# ZHSD-DDR3L.net
KiCad netlist of a schematic drawn in Altium Designer
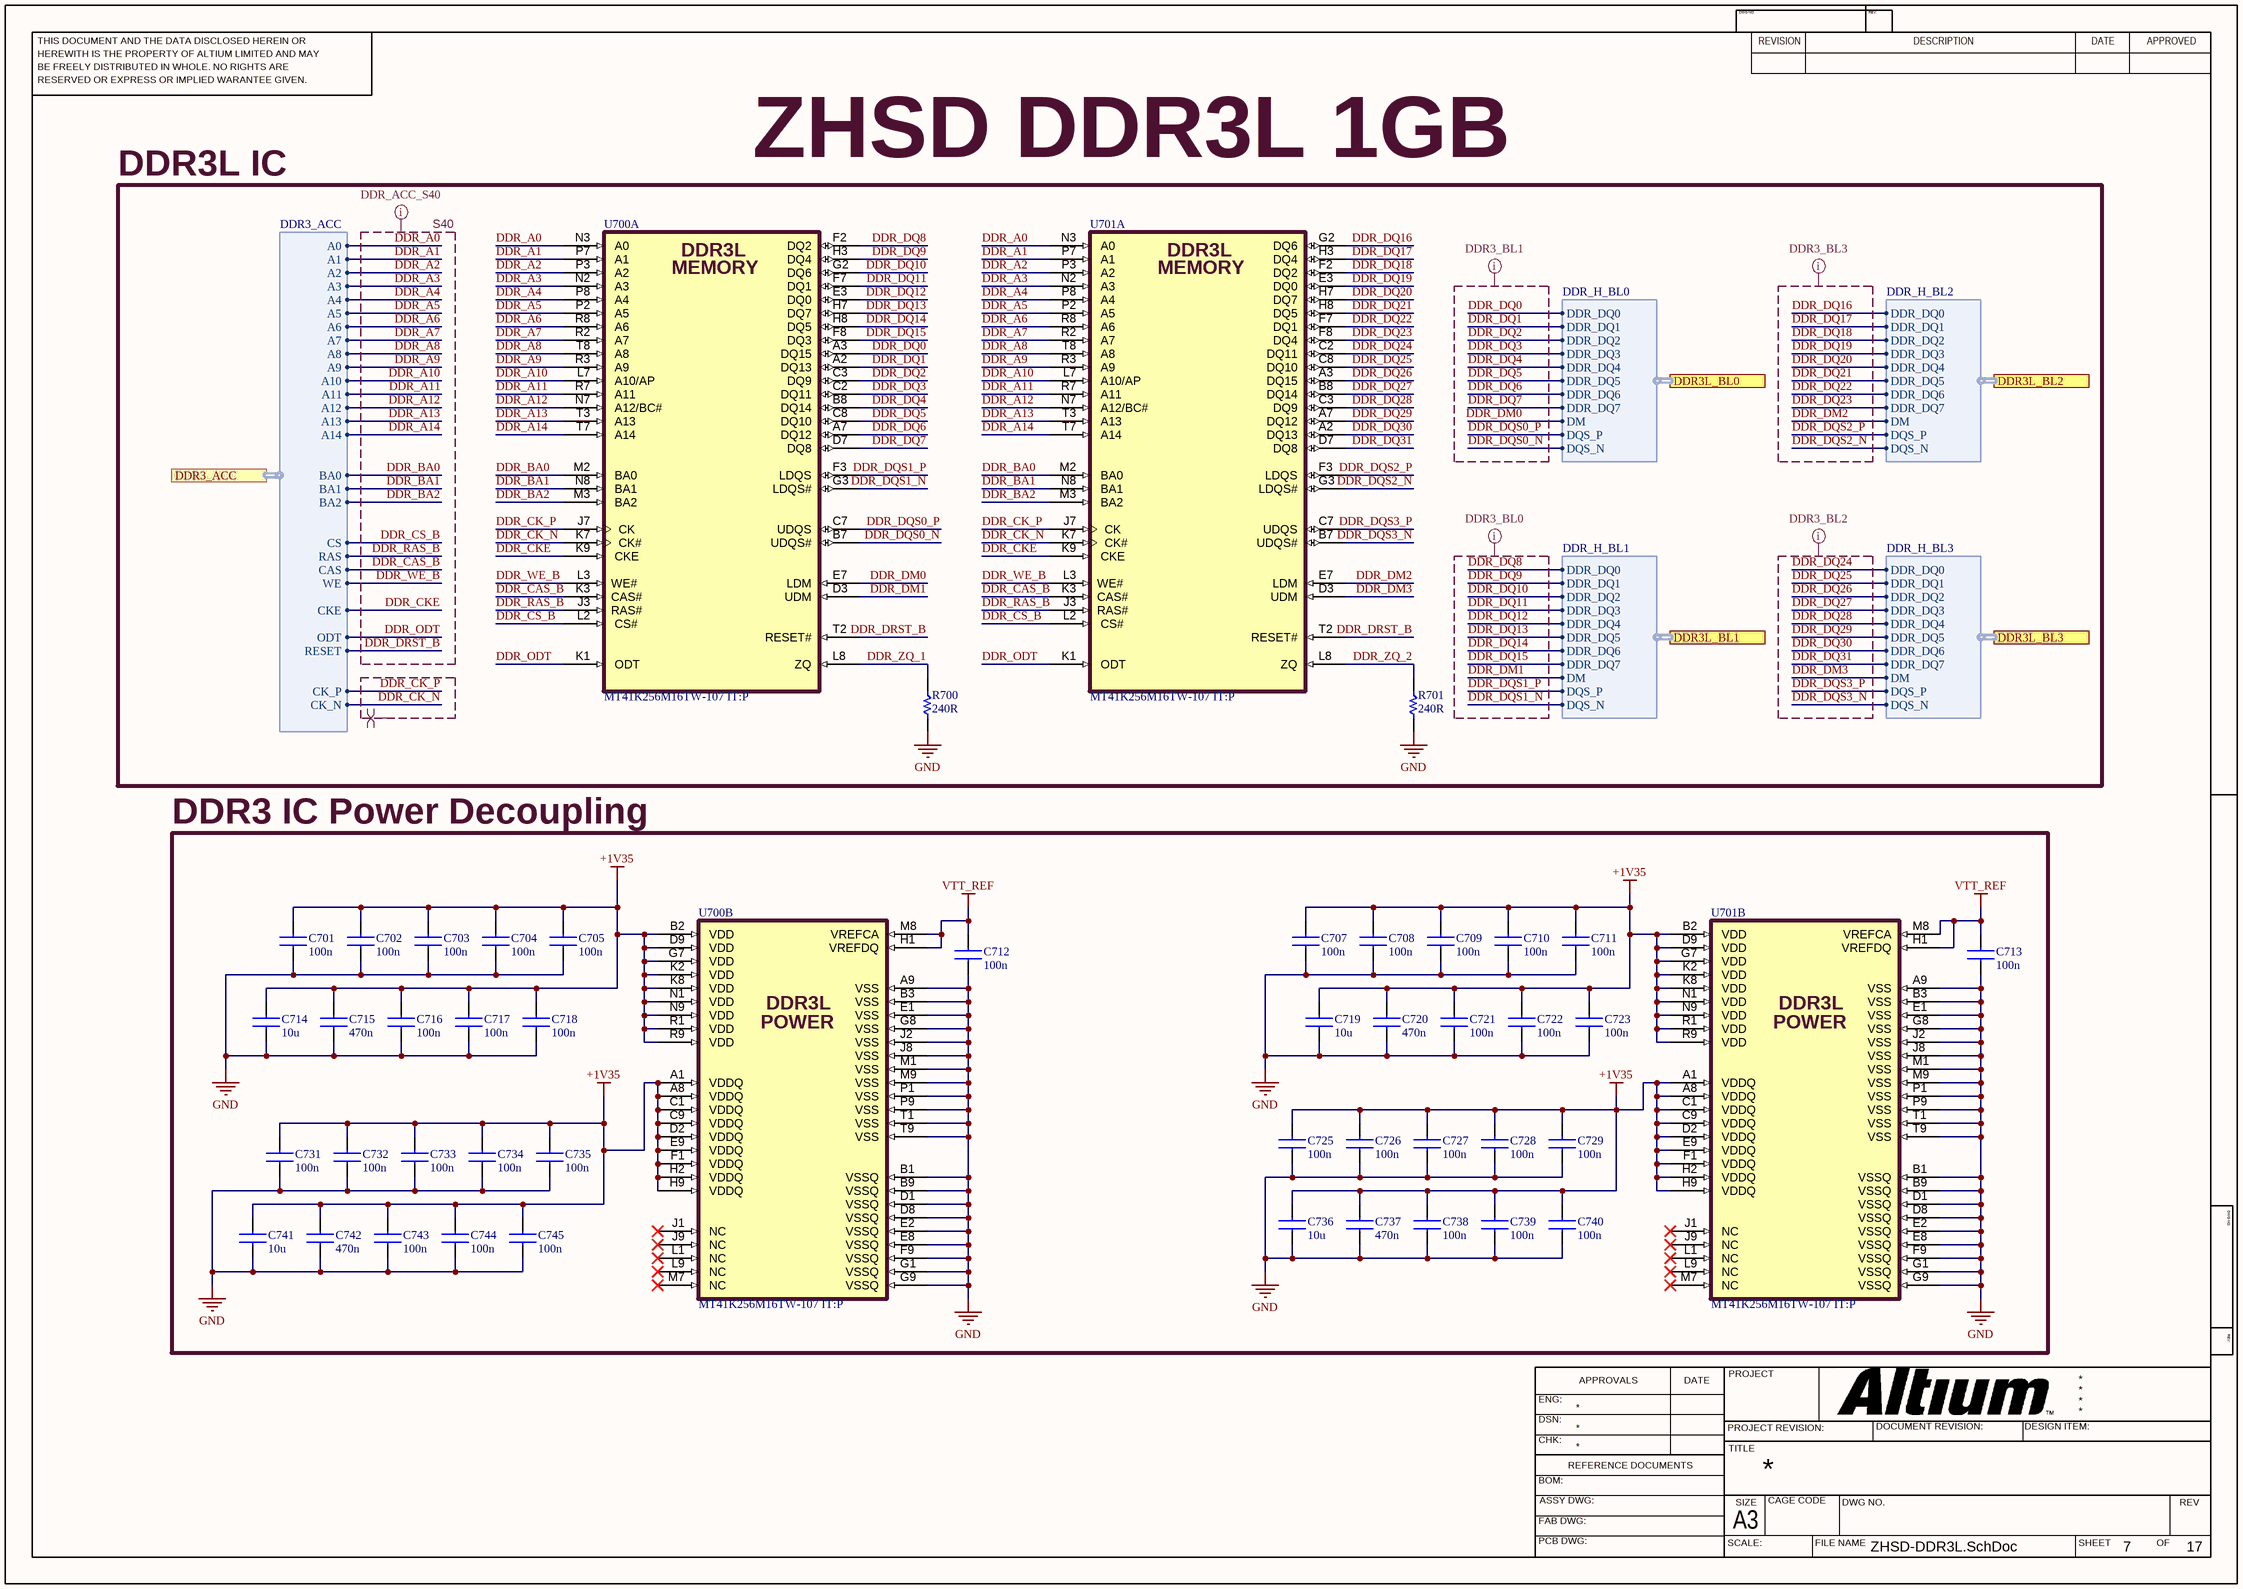
[diagram p0: ZHSD-DDR3L.SchDoc]

(export (version "E")
  (design (tool "Eeschema 10.0.6"))
  (components
    (comp (ref "C701")
      (value "100n")
      (footprint "0402CAPC1005X06N")
      (description "CAP CER 0.1UF 16V X7R 0402 (1005) ±10%")
      (fields (field (name "MANUFACTURER") "Murata Electronics") (field (name "MPN") "GRM155R71C104KA88J"))
      (libsource (lib "UK_Library_SCH") (part "GRM155R71C104KA88J"))
    )
    (comp (ref "C702")
      (value "100n")
      (footprint "0402CAPC1005X06N")
      (description "CAP CER 0.1UF 16V X7R 0402 (1005) ±10%")
      (fields (field (name "MANUFACTURER") "Murata Electronics") (field (name "MPN") "GRM155R71C104KA88J"))
      (libsource (lib "UK_Library_SCH") (part "GRM155R71C104KA88J"))
    )
    (comp (ref "C703")
      (value "100n")
      (footprint "0402CAPC1005X06N")
      (description "CAP CER 0.1UF 16V X7R 0402 (1005) ±10%")
      (fields (field (name "MANUFACTURER") "Murata Electronics") (field (name "MPN") "GRM155R71C104KA88J"))
      (libsource (lib "UK_Library_SCH") (part "GRM155R71C104KA88J"))
    )
    (comp (ref "C704")
      (value "100n")
      (footprint "0402CAPC1005X06N")
      (description "CAP CER 0.1UF 16V X7R 0402 (1005) ±10%")
      (fields (field (name "MANUFACTURER") "Murata Electronics") (field (name "MPN") "GRM155R71C104KA88J"))
      (libsource (lib "UK_Library_SCH") (part "GRM155R71C104KA88J"))
    )
    (comp (ref "C705")
      (value "100n")
      (footprint "0402CAPC1005X06N")
      (description "CAP CER 0.1UF 16V X7R 0402 (1005) ±10%")
      (fields (field (name "MANUFACTURER") "Murata Electronics") (field (name "MPN") "GRM155R71C104KA88J"))
      (libsource (lib "UK_Library_SCH") (part "GRM155R71C104KA88J"))
    )
    (comp (ref "C707")
      (value "100n")
      (footprint "0402CAPC1005X06N")
      (description "CAP CER 0.1UF 16V X7R 0402 (1005) ±10%")
      (fields (field (name "MANUFACTURER") "Murata Electronics") (field (name "MPN") "GRM155R71C104KA88J"))
      (libsource (lib "UK_Library_SCH") (part "GRM155R71C104KA88J"))
    )
    (comp (ref "C708")
      (value "100n")
      (footprint "0402CAPC1005X06N")
      (description "CAP CER 0.1UF 16V X7R 0402 (1005) ±10%")
      (fields (field (name "MANUFACTURER") "Murata Electronics") (field (name "MPN") "GRM155R71C104KA88J"))
      (libsource (lib "UK_Library_SCH") (part "GRM155R71C104KA88J"))
    )
    (comp (ref "C709")
      (value "100n")
      (footprint "0402CAPC1005X06N")
      (description "CAP CER 0.1UF 16V X7R 0402 (1005) ±10%")
      (fields (field (name "MANUFACTURER") "Murata Electronics") (field (name "MPN") "GRM155R71C104KA88J"))
      (libsource (lib "UK_Library_SCH") (part "GRM155R71C104KA88J"))
    )
    (comp (ref "C710")
      (value "100n")
      (footprint "0402CAPC1005X06N")
      (description "CAP CER 0.1UF 16V X7R 0402 (1005) ±10%")
      (fields (field (name "MANUFACTURER") "Murata Electronics") (field (name "MPN") "GRM155R71C104KA88J"))
      (libsource (lib "UK_Library_SCH") (part "GRM155R71C104KA88J"))
    )
    (comp (ref "C711")
      (value "100n")
      (footprint "0402CAPC1005X06N")
      (description "CAP CER 0.1UF 16V X7R 0402 (1005) ±10%")
      (fields (field (name "MANUFACTURER") "Murata Electronics") (field (name "MPN") "GRM155R71C104KA88J"))
      (libsource (lib "UK_Library_SCH") (part "GRM155R71C104KA88J"))
    )
    (comp (ref "C712")
      (value "100n")
      (footprint "0402CAPC1005X06N")
      (description "CAP CER 0.1UF 16V X7R 0402 (1005) ±10%")
      (fields (field (name "MANUFACTURER") "Murata Electronics") (field (name "MPN") "GRM155R71C104KA88J"))
      (libsource (lib "UK_Library_SCH") (part "GRM155R71C104KA88J"))
    )
    (comp (ref "C713")
      (value "100n")
      (footprint "0402CAPC1005X06N")
      (description "CAP CER 0.1UF 16V X7R 0402 (1005) ±10%")
      (fields (field (name "MANUFACTURER") "Murata Electronics") (field (name "MPN") "GRM155R71C104KA88J"))
      (libsource (lib "UK_Library_SCH") (part "GRM155R71C104KA88J"))
    )
    (comp (ref "C714")
      (value "10u")
      (footprint "0603CAPC1608X09N")
      (description "CAP CER 10UF 10V X7R 0603 (1608) ±20%")
      (fields (field (name "MANUFACTURER") "Murata Electronics") (field (name "MPN") "GRM188Z71A106MA73D"))
      (libsource (lib "UK_Library") (part "GRM188Z71A106MA73D"))
    )
    (comp (ref "C715")
      (value "470n")
      (footprint "0402CAPC1005X06N")
      (description "CAP CER 0.47UF 6.3V X5R 0402(1005) ±10%")
      (fields (field (name "MANUFACTURER") "Murata Electronics") (field (name "MPN") "GRM155R60J474KE19D"))
      (libsource (lib "UK_Library") (part "GRM155R60J474KE19D"))
    )
    (comp (ref "C716")
      (value "100n")
      (footprint "0402CAPC1005X06N")
      (description "CAP CER 0.1UF 16V X7R 0402 (1005) ±10%")
      (fields (field (name "MANUFACTURER") "Murata Electronics") (field (name "MPN") "GRM155R71C104KA88J"))
      (libsource (lib "UK_Library_SCH") (part "GRM155R71C104KA88J"))
    )
    (comp (ref "C717")
      (value "100n")
      (footprint "0402CAPC1005X06N")
      (description "CAP CER 0.1UF 16V X7R 0402 (1005) ±10%")
      (fields (field (name "MANUFACTURER") "Murata Electronics") (field (name "MPN") "GRM155R71C104KA88J"))
      (libsource (lib "UK_Library_SCH") (part "GRM155R71C104KA88J"))
    )
    (comp (ref "C718")
      (value "100n")
      (footprint "0402CAPC1005X06N")
      (description "CAP CER 0.1UF 16V X7R 0402 (1005) ±10%")
      (fields (field (name "MANUFACTURER") "Murata Electronics") (field (name "MPN") "GRM155R71C104KA88J"))
      (libsource (lib "UK_Library_SCH") (part "GRM155R71C104KA88J"))
    )
    (comp (ref "C719")
      (value "10u")
      (footprint "0603CAPC1608X09N")
      (description "CAP CER 10UF 10V X7R 0603 (1608) ±20%")
      (fields (field (name "MANUFACTURER") "Murata Electronics") (field (name "MPN") "GRM188Z71A106MA73D"))
      (libsource (lib "UK_Library") (part "GRM188Z71A106MA73D"))
    )
    (comp (ref "C720")
      (value "470n")
      (footprint "0402CAPC1005X06N")
      (description "CAP CER 0.47UF 6.3V X5R 0402(1005) ±10%")
      (fields (field (name "MANUFACTURER") "Murata Electronics") (field (name "MPN") "GRM155R60J474KE19D"))
      (libsource (lib "UK_Library") (part "GRM155R60J474KE19D"))
    )
    (comp (ref "C721")
      (value "100n")
      (footprint "0402CAPC1005X06N")
      (description "CAP CER 0.1UF 16V X7R 0402 (1005) ±10%")
      (fields (field (name "MANUFACTURER") "Murata Electronics") (field (name "MPN") "GRM155R71C104KA88J"))
      (libsource (lib "UK_Library_SCH") (part "GRM155R71C104KA88J"))
    )
    (comp (ref "C722")
      (value "100n")
      (footprint "0402CAPC1005X06N")
      (description "CAP CER 0.1UF 16V X7R 0402 (1005) ±10%")
      (fields (field (name "MANUFACTURER") "Murata Electronics") (field (name "MPN") "GRM155R71C104KA88J"))
      (libsource (lib "UK_Library_SCH") (part "GRM155R71C104KA88J"))
    )
    (comp (ref "C723")
      (value "100n")
      (footprint "0402CAPC1005X06N")
      (description "CAP CER 0.1UF 16V X7R 0402 (1005) ±10%")
      (fields (field (name "MANUFACTURER") "Murata Electronics") (field (name "MPN") "GRM155R71C104KA88J"))
      (libsource (lib "UK_Library_SCH") (part "GRM155R71C104KA88J"))
    )
    (comp (ref "C725")
      (value "100n")
      (footprint "0402CAPC1005X06N")
      (description "CAP CER 0.1UF 16V X7R 0402 (1005) ±10%")
      (fields (field (name "MANUFACTURER") "Murata Electronics") (field (name "MPN") "GRM155R71C104KA88J"))
      (libsource (lib "UK_Library_SCH") (part "GRM155R71C104KA88J"))
    )
    (comp (ref "C726")
      (value "100n")
      (footprint "0402CAPC1005X06N")
      (description "CAP CER 0.1UF 16V X7R 0402 (1005) ±10%")
      (fields (field (name "MANUFACTURER") "Murata Electronics") (field (name "MPN") "GRM155R71C104KA88J"))
      (libsource (lib "UK_Library_SCH") (part "GRM155R71C104KA88J"))
    )
    (comp (ref "C727")
      (value "100n")
      (footprint "0402CAPC1005X06N")
      (description "CAP CER 0.1UF 16V X7R 0402 (1005) ±10%")
      (fields (field (name "MANUFACTURER") "Murata Electronics") (field (name "MPN") "GRM155R71C104KA88J"))
      (libsource (lib "UK_Library_SCH") (part "GRM155R71C104KA88J"))
    )
    (comp (ref "C728")
      (value "100n")
      (footprint "0402CAPC1005X06N")
      (description "CAP CER 0.1UF 16V X7R 0402 (1005) ±10%")
      (fields (field (name "MANUFACTURER") "Murata Electronics") (field (name "MPN") "GRM155R71C104KA88J"))
      (libsource (lib "UK_Library_SCH") (part "GRM155R71C104KA88J"))
    )
    (comp (ref "C729")
      (value "100n")
      (footprint "0402CAPC1005X06N")
      (description "CAP CER 0.1UF 16V X7R 0402 (1005) ±10%")
      (fields (field (name "MANUFACTURER") "Murata Electronics") (field (name "MPN") "GRM155R71C104KA88J"))
      (libsource (lib "UK_Library_SCH") (part "GRM155R71C104KA88J"))
    )
    (comp (ref "C731")
      (value "100n")
      (footprint "0402CAPC1005X06N")
      (description "CAP CER 0.1UF 16V X7R 0402 (1005) ±10%")
      (fields (field (name "MANUFACTURER") "Murata Electronics") (field (name "MPN") "GRM155R71C104KA88J"))
      (libsource (lib "UK_Library_SCH") (part "GRM155R71C104KA88J"))
    )
    (comp (ref "C732")
      (value "100n")
      (footprint "0402CAPC1005X06N")
      (description "CAP CER 0.1UF 16V X7R 0402 (1005) ±10%")
      (fields (field (name "MANUFACTURER") "Murata Electronics") (field (name "MPN") "GRM155R71C104KA88J"))
      (libsource (lib "UK_Library_SCH") (part "GRM155R71C104KA88J"))
    )
    (comp (ref "C733")
      (value "100n")
      (footprint "0402CAPC1005X06N")
      (description "CAP CER 0.1UF 16V X7R 0402 (1005) ±10%")
      (fields (field (name "MANUFACTURER") "Murata Electronics") (field (name "MPN") "GRM155R71C104KA88J"))
      (libsource (lib "UK_Library_SCH") (part "GRM155R71C104KA88J"))
    )
    (comp (ref "C734")
      (value "100n")
      (footprint "0402CAPC1005X06N")
      (description "CAP CER 0.1UF 16V X7R 0402 (1005) ±10%")
      (fields (field (name "MANUFACTURER") "Murata Electronics") (field (name "MPN") "GRM155R71C104KA88J"))
      (libsource (lib "UK_Library_SCH") (part "GRM155R71C104KA88J"))
    )
    (comp (ref "C735")
      (value "100n")
      (footprint "0402CAPC1005X06N")
      (description "CAP CER 0.1UF 16V X7R 0402 (1005) ±10%")
      (fields (field (name "MANUFACTURER") "Murata Electronics") (field (name "MPN") "GRM155R71C104KA88J"))
      (libsource (lib "UK_Library_SCH") (part "GRM155R71C104KA88J"))
    )
    (comp (ref "C736")
      (value "10u")
      (footprint "0603CAPC1608X09N")
      (description "CAP CER 10UF 10V X7R 0603 (1608) ±20%")
      (fields (field (name "MANUFACTURER") "Murata Electronics") (field (name "MPN") "GRM188Z71A106MA73D"))
      (libsource (lib "UK_Library") (part "GRM188Z71A106MA73D"))
    )
    (comp (ref "C737")
      (value "470n")
      (footprint "0402CAPC1005X06N")
      (description "CAP CER 0.47UF 6.3V X5R 0402(1005) ±10%")
      (fields (field (name "MANUFACTURER") "Murata Electronics") (field (name "MPN") "GRM155R60J474KE19D"))
      (libsource (lib "UK_Library") (part "GRM155R60J474KE19D"))
    )
    (comp (ref "C738")
      (value "100n")
      (footprint "0402CAPC1005X06N")
      (description "CAP CER 0.1UF 16V X7R 0402 (1005) ±10%")
      (fields (field (name "MANUFACTURER") "Murata Electronics") (field (name "MPN") "GRM155R71C104KA88J"))
      (libsource (lib "UK_Library_SCH") (part "GRM155R71C104KA88J"))
    )
    (comp (ref "C739")
      (value "100n")
      (footprint "0402CAPC1005X06N")
      (description "CAP CER 0.1UF 16V X7R 0402 (1005) ±10%")
      (fields (field (name "MANUFACTURER") "Murata Electronics") (field (name "MPN") "GRM155R71C104KA88J"))
      (libsource (lib "UK_Library_SCH") (part "GRM155R71C104KA88J"))
    )
    (comp (ref "C740")
      (value "100n")
      (footprint "0402CAPC1005X06N")
      (description "CAP CER 0.1UF 16V X7R 0402 (1005) ±10%")
      (fields (field (name "MANUFACTURER") "Murata Electronics") (field (name "MPN") "GRM155R71C104KA88J"))
      (libsource (lib "UK_Library_SCH") (part "GRM155R71C104KA88J"))
    )
    (comp (ref "C741")
      (value "10u")
      (footprint "0603CAPC1608X09N")
      (description "CAP CER 10UF 10V X7R 0603 (1608) ±20%")
      (fields (field (name "MANUFACTURER") "Murata Electronics") (field (name "MPN") "GRM188Z71A106MA73D"))
      (libsource (lib "UK_Library") (part "GRM188Z71A106MA73D"))
    )
    (comp (ref "C742")
      (value "470n")
      (footprint "0402CAPC1005X06N")
      (description "CAP CER 0.47UF 6.3V X5R 0402(1005) ±10%")
      (fields (field (name "MANUFACTURER") "Murata Electronics") (field (name "MPN") "GRM155R60J474KE19D"))
      (libsource (lib "UK_Library") (part "GRM155R60J474KE19D"))
    )
    (comp (ref "C743")
      (value "100n")
      (footprint "0402CAPC1005X06N")
      (description "CAP CER 0.1UF 16V X7R 0402 (1005) ±10%")
      (fields (field (name "MANUFACTURER") "Murata Electronics") (field (name "MPN") "GRM155R71C104KA88J"))
      (libsource (lib "UK_Library_SCH") (part "GRM155R71C104KA88J"))
    )
    (comp (ref "C744")
      (value "100n")
      (footprint "0402CAPC1005X06N")
      (description "CAP CER 0.1UF 16V X7R 0402 (1005) ±10%")
      (fields (field (name "MANUFACTURER") "Murata Electronics") (field (name "MPN") "GRM155R71C104KA88J"))
      (libsource (lib "UK_Library_SCH") (part "GRM155R71C104KA88J"))
    )
    (comp (ref "C745")
      (value "100n")
      (footprint "0402CAPC1005X06N")
      (description "CAP CER 0.1UF 16V X7R 0402 (1005) ±10%")
      (fields (field (name "MANUFACTURER") "Murata Electronics") (field (name "MPN") "GRM155R71C104KA88J"))
      (libsource (lib "UK_Library_SCH") (part "GRM155R71C104KA88J"))
    )
    (comp (ref "R700")
      (value "240R")
      (footprint "0402RESC1005X04N")
      (description "RES 240 OHM 1% 1/16W 0402 (1005)")
      (fields (field (name "MANUFACTURER") "YAGEO") (field (name "MPN") "RC0402FR-07240RL"))
      (libsource (lib "UK_Library") (part "RC0402FR-07240RL"))
    )
    (comp (ref "R701")
      (value "240R")
      (footprint "0402RESC1005X04N")
      (description "RES 240 OHM 1% 1/16W 0402 (1005)")
      (fields (field (name "MANUFACTURER") "YAGEO") (field (name "MPN") "RC0402FR-07240RL"))
      (libsource (lib "UK_Library") (part "RC0402FR-07240RL"))
    )
    (comp (ref "U700")
      (value "MT41K256M16TW-107 IT:P")
      (footprint "BGA96C80P9X16_900X1400X110")
      (description "SDRAM - DDR3L Memory IC 4Gbit Parallel 933 MHz 20 ns 96-FBGA (8x14)")
      (fields (field (name "MANUFACTURER") "Micron Technology Inc."))
      (libsource (lib "") (part "MT41K256M16TW-107 IT{colon}P_1"))
    )
    (comp (ref "U701")
      (value "MT41K256M16TW-107 IT:P")
      (footprint "BGA96C80P9X16_900X1400X110")
      (description "SDRAM - DDR3L Memory IC 4Gbit Parallel 933 MHz 20 ns 96-FBGA (8x14)")
      (fields (field (name "MANUFACTURER") "Micron Technology Inc."))
      (libsource (lib "UK_Library") (part "MT41K256M16TW-107 IT{colon}P"))
    )
  )
  (nets
    (net (code "6") (name "+1V35") (class "Default")
      (node (ref "C701") (pin "2") (pinfunction "2_2") (pintype "passive"))
      (node (ref "C702") (pin "2") (pinfunction "2_2") (pintype "passive"))
      (node (ref "C703") (pin "2") (pinfunction "2_2") (pintype "passive"))
      (node (ref "C704") (pin "2") (pinfunction "2_2") (pintype "passive"))
      (node (ref "C705") (pin "2") (pinfunction "2_2") (pintype "passive"))
      (node (ref "C707") (pin "2") (pinfunction "2_2") (pintype "passive"))
      (node (ref "C708") (pin "2") (pinfunction "2_2") (pintype "passive"))
      (node (ref "C709") (pin "2") (pinfunction "2_2") (pintype "passive"))
      (node (ref "C710") (pin "2") (pinfunction "2_2") (pintype "passive"))
      (node (ref "C711") (pin "2") (pinfunction "2_2") (pintype "passive"))
      (node (ref "C714") (pin "2") (pinfunction "2_2") (pintype "passive"))
      (node (ref "C715") (pin "2") (pinfunction "2_2") (pintype "passive"))
      (node (ref "C716") (pin "2") (pinfunction "2_2") (pintype "passive"))
      (node (ref "C717") (pin "2") (pinfunction "2_2") (pintype "passive"))
      (node (ref "C718") (pin "2") (pinfunction "2_2") (pintype "passive"))
      (node (ref "C719") (pin "2") (pinfunction "2_2") (pintype "passive"))
      (node (ref "C720") (pin "2") (pinfunction "2_2") (pintype "passive"))
      (node (ref "C721") (pin "2") (pinfunction "2_2") (pintype "passive"))
      (node (ref "C722") (pin "2") (pinfunction "2_2") (pintype "passive"))
      (node (ref "C723") (pin "2") (pinfunction "2_2") (pintype "passive"))
      (node (ref "C725") (pin "2") (pinfunction "2_2") (pintype "passive"))
      (node (ref "C726") (pin "2") (pinfunction "2_2") (pintype "passive"))
      (node (ref "C727") (pin "2") (pinfunction "2_2") (pintype "passive"))
      (node (ref "C728") (pin "2") (pinfunction "2_2") (pintype "passive"))
      (node (ref "C729") (pin "2") (pinfunction "2_2") (pintype "passive"))
      (node (ref "C731") (pin "2") (pinfunction "2_2") (pintype "passive"))
      (node (ref "C732") (pin "2") (pinfunction "2_2") (pintype "passive"))
      (node (ref "C733") (pin "2") (pinfunction "2_2") (pintype "passive"))
      (node (ref "C734") (pin "2") (pinfunction "2_2") (pintype "passive"))
      (node (ref "C735") (pin "2") (pinfunction "2_2") (pintype "passive"))
      (node (ref "C736") (pin "2") (pinfunction "2_2") (pintype "passive"))
      (node (ref "C737") (pin "2") (pinfunction "2_2") (pintype "passive"))
      (node (ref "C738") (pin "2") (pinfunction "2_2") (pintype "passive"))
      (node (ref "C739") (pin "2") (pinfunction "2_2") (pintype "passive"))
      (node (ref "C740") (pin "2") (pinfunction "2_2") (pintype "passive"))
      (node (ref "C741") (pin "2") (pinfunction "2_2") (pintype "passive"))
      (node (ref "C742") (pin "2") (pinfunction "2_2") (pintype "passive"))
      (node (ref "C743") (pin "2") (pinfunction "2_2") (pintype "passive"))
      (node (ref "C744") (pin "2") (pinfunction "2_2") (pintype "passive"))
      (node (ref "C745") (pin "2") (pinfunction "2_2") (pintype "passive"))
      (node (ref "U700") (pin "A1") (pinfunction "_VDDQ_A1") (pintype "input"))
      (node (ref "U700") (pin "A8") (pinfunction "_VDDQ_A8") (pintype "input"))
      (node (ref "U700") (pin "B2") (pinfunction "_VDD_B2") (pintype "input"))
      (node (ref "U700") (pin "C1") (pinfunction "_VDDQ_C1") (pintype "input"))
      (node (ref "U700") (pin "C9") (pinfunction "_VDDQ_C9") (pintype "input"))
      (node (ref "U700") (pin "D2") (pinfunction "_VDDQ_D2") (pintype "input"))
      (node (ref "U700") (pin "D9") (pinfunction "_VDD_D9") (pintype "input"))
      (node (ref "U700") (pin "E9") (pinfunction "_VDDQ_E9") (pintype "input"))
      (node (ref "U700") (pin "F1") (pinfunction "_VDDQ_F1") (pintype "input"))
      (node (ref "U700") (pin "G7") (pinfunction "_VDD_G7") (pintype "input"))
      (node (ref "U700") (pin "H2") (pinfunction "_VDDQ_H2") (pintype "input"))
      (node (ref "U700") (pin "H9") (pinfunction "_VDDQ_H9") (pintype "input"))
      (node (ref "U700") (pin "K2") (pinfunction "_VDD_K2") (pintype "input"))
      (node (ref "U700") (pin "K8") (pinfunction "_VDD_K8") (pintype "input"))
      (node (ref "U700") (pin "N1") (pinfunction "_VDD_N1") (pintype "input"))
      (node (ref "U700") (pin "N9") (pinfunction "_VDD_N9") (pintype "input"))
      (node (ref "U700") (pin "R1") (pinfunction "_VDD_R1") (pintype "input"))
      (node (ref "U700") (pin "R9") (pinfunction "_VDD_R9") (pintype "input"))
      (node (ref "U701") (pin "A1") (pinfunction "_VDDQ_A1") (pintype "input"))
      (node (ref "U701") (pin "A8") (pinfunction "_VDDQ_A8") (pintype "input"))
      (node (ref "U701") (pin "B2") (pinfunction "_VDD_B2") (pintype "input"))
      (node (ref "U701") (pin "C1") (pinfunction "_VDDQ_C1") (pintype "input"))
      (node (ref "U701") (pin "C9") (pinfunction "_VDDQ_C9") (pintype "input"))
      (node (ref "U701") (pin "D2") (pinfunction "_VDDQ_D2") (pintype "input"))
      (node (ref "U701") (pin "D9") (pinfunction "_VDD_D9") (pintype "input"))
      (node (ref "U701") (pin "E9") (pinfunction "_VDDQ_E9") (pintype "input"))
      (node (ref "U701") (pin "F1") (pinfunction "_VDDQ_F1") (pintype "input"))
      (node (ref "U701") (pin "G7") (pinfunction "_VDD_G7") (pintype "input"))
      (node (ref "U701") (pin "H2") (pinfunction "_VDDQ_H2") (pintype "input"))
      (node (ref "U701") (pin "H9") (pinfunction "_VDDQ_H9") (pintype "input"))
      (node (ref "U701") (pin "K2") (pinfunction "_VDD_K2") (pintype "input"))
      (node (ref "U701") (pin "K8") (pinfunction "_VDD_K8") (pintype "input"))
      (node (ref "U701") (pin "N1") (pinfunction "_VDD_N1") (pintype "input"))
      (node (ref "U701") (pin "N9") (pinfunction "_VDD_N9") (pintype "input"))
      (node (ref "U701") (pin "R1") (pinfunction "_VDD_R1") (pintype "input"))
      (node (ref "U701") (pin "R9") (pinfunction "_VDD_R9") (pintype "input"))
    )
    (net (code "7") (name "/DDR_A0") (class "Default")
      (node (ref "U700") (pin "N3") (pinfunction "_A0_N3") (pintype "input"))
      (node (ref "U701") (pin "N3") (pinfunction "_A0_N3") (pintype "input"))
    )
    (net (code "8") (name "/DDR_A1") (class "Default")
      (node (ref "U700") (pin "P7") (pinfunction "_A1_P7") (pintype "input"))
      (node (ref "U701") (pin "P7") (pinfunction "_A1_P7") (pintype "input"))
    )
    (net (code "9") (name "/DDR_A2") (class "Default")
      (node (ref "U700") (pin "P3") (pinfunction "_A2_P3") (pintype "input"))
      (node (ref "U701") (pin "P3") (pinfunction "_A2_P3") (pintype "input"))
    )
    (net (code "10") (name "/DDR_A3") (class "Default")
      (node (ref "U700") (pin "N2") (pinfunction "_A3_N2") (pintype "input"))
      (node (ref "U701") (pin "N2") (pinfunction "_A3_N2") (pintype "input"))
    )
    (net (code "11") (name "/DDR_A4") (class "Default")
      (node (ref "U700") (pin "P8") (pinfunction "_A4_P8") (pintype "input"))
      (node (ref "U701") (pin "P8") (pinfunction "_A4_P8") (pintype "input"))
    )
    (net (code "12") (name "/DDR_A5") (class "Default")
      (node (ref "U700") (pin "P2") (pinfunction "_A5_P2") (pintype "input"))
      (node (ref "U701") (pin "P2") (pinfunction "_A5_P2") (pintype "input"))
    )
    (net (code "13") (name "/DDR_A6") (class "Default")
      (node (ref "U700") (pin "R8") (pinfunction "_A6_R8") (pintype "input"))
      (node (ref "U701") (pin "R8") (pinfunction "_A6_R8") (pintype "input"))
    )
    (net (code "14") (name "/DDR_A7") (class "Default")
      (node (ref "U700") (pin "R2") (pinfunction "_A7_R2") (pintype "input"))
      (node (ref "U701") (pin "R2") (pinfunction "_A7_R2") (pintype "input"))
    )
    (net (code "15") (name "/DDR_A8") (class "Default")
      (node (ref "U700") (pin "T8") (pinfunction "_A8_T8") (pintype "input"))
      (node (ref "U701") (pin "T8") (pinfunction "_A8_T8") (pintype "input"))
    )
    (net (code "16") (name "/DDR_A9") (class "Default")
      (node (ref "U700") (pin "R3") (pinfunction "_A9_R3") (pintype "input"))
      (node (ref "U701") (pin "R3") (pinfunction "_A9_R3") (pintype "input"))
    )
    (net (code "17") (name "/DDR_A10") (class "Default")
      (node (ref "U700") (pin "L7") (pinfunction "_A10/AP_L7") (pintype "input"))
      (node (ref "U701") (pin "L7") (pinfunction "_A10/AP_L7") (pintype "input"))
    )
    (net (code "18") (name "/DDR_A11") (class "Default")
      (node (ref "U700") (pin "R7") (pinfunction "_A11_R7") (pintype "input"))
      (node (ref "U701") (pin "R7") (pinfunction "_A11_R7") (pintype "input"))
    )
    (net (code "19") (name "/DDR_A12") (class "Default")
      (node (ref "U700") (pin "N7") (pinfunction "_A12/BC#_N7") (pintype "input"))
      (node (ref "U701") (pin "N7") (pinfunction "_A12/BC#_N7") (pintype "input"))
    )
    (net (code "20") (name "/DDR_A13") (class "Default")
      (node (ref "U700") (pin "T3") (pinfunction "_A13_T3") (pintype "input"))
      (node (ref "U701") (pin "T3") (pinfunction "_A13_T3") (pintype "input"))
    )
    (net (code "21") (name "/DDR_A14") (class "Default")
      (node (ref "U700") (pin "T7") (pinfunction "_A14_T7") (pintype "input"))
      (node (ref "U701") (pin "T7") (pinfunction "_A14_T7") (pintype "input"))
    )
    (net (code "22") (name "/DDR_BA0") (class "Default")
      (node (ref "U700") (pin "M2") (pinfunction "_BA0_M2") (pintype "input"))
      (node (ref "U701") (pin "M2") (pinfunction "_BA0_M2") (pintype "input"))
    )
    (net (code "23") (name "/DDR_BA1") (class "Default")
      (node (ref "U700") (pin "N8") (pinfunction "_BA1_N8") (pintype "input"))
      (node (ref "U701") (pin "N8") (pinfunction "_BA1_N8") (pintype "input"))
    )
    (net (code "24") (name "/DDR_BA2") (class "Default")
      (node (ref "U700") (pin "M3") (pinfunction "_BA2_M3") (pintype "input"))
      (node (ref "U701") (pin "M3") (pinfunction "_BA2_M3") (pintype "input"))
    )
    (net (code "25") (name "/DDR_CAS_B") (class "Default")
      (node (ref "U700") (pin "K3") (pinfunction "CAS#_K3") (pintype "input"))
      (node (ref "U701") (pin "K3") (pinfunction "CAS#_K3") (pintype "input"))
    )
    (net (code "26") (name "/DDR_CKE") (class "Default")
      (node (ref "U700") (pin "K9") (pinfunction "_CKE_K9") (pintype "input"))
      (node (ref "U701") (pin "K9") (pinfunction "_CKE_K9") (pintype "input"))
    )
    (net (code "27") (name "/DDR_CK_N") (class "Default")
      (node (ref "U700") (pin "K7") (pinfunction "_CK#_K7") (pintype "input"))
      (node (ref "U701") (pin "K7") (pinfunction "_CK#_K7") (pintype "input"))
    )
    (net (code "28") (name "/DDR_CK_P") (class "Default")
      (node (ref "U700") (pin "J7") (pinfunction "_CK_J7") (pintype "input"))
      (node (ref "U701") (pin "J7") (pinfunction "_CK_J7") (pintype "input"))
    )
    (net (code "29") (name "/DDR_CS_B") (class "Default")
      (node (ref "U700") (pin "L2") (pinfunction "_CS#_L2") (pintype "input"))
      (node (ref "U701") (pin "L2") (pinfunction "_CS#_L2") (pintype "input"))
    )
    (net (code "30") (name "/DDR_DM0") (class "Default")
      (node (ref "U700") (pin "E7") (pinfunction "_LDM_E7") (pintype "input"))
    )
    (net (code "31") (name "/DDR_DM1") (class "Default")
      (node (ref "U700") (pin "D3") (pinfunction "_UDM_D3") (pintype "input"))
    )
    (net (code "32") (name "/DDR_DM2") (class "Default")
      (node (ref "U701") (pin "E7") (pinfunction "_LDM_E7") (pintype "input"))
    )
    (net (code "33") (name "/DDR_DM3") (class "Default")
      (node (ref "U701") (pin "D3") (pinfunction "_UDM_D3") (pintype "input"))
    )
    (net (code "34") (name "/DDR_DQ0") (class "Default")
      (node (ref "U700") (pin "A3") (pinfunction "_DQ15_A3") (pintype "bidirectional"))
    )
    (net (code "35") (name "/DDR_DQ1") (class "Default")
      (node (ref "U700") (pin "A2") (pinfunction "_DQ13_A2") (pintype "bidirectional"))
    )
    (net (code "36") (name "/DDR_DQ2") (class "Default")
      (node (ref "U700") (pin "C3") (pinfunction "_DQ9_C3") (pintype "bidirectional"))
    )
    (net (code "37") (name "/DDR_DQ3") (class "Default")
      (node (ref "U700") (pin "C2") (pinfunction "_DQ11_C2") (pintype "bidirectional"))
    )
    (net (code "38") (name "/DDR_DQ4") (class "Default")
      (node (ref "U700") (pin "B8") (pinfunction "_DQ14_B8") (pintype "bidirectional"))
    )
    (net (code "39") (name "/DDR_DQ5") (class "Default")
      (node (ref "U700") (pin "C8") (pinfunction "_DQ10_C8") (pintype "bidirectional"))
    )
    (net (code "40") (name "/DDR_DQ6") (class "Default")
      (node (ref "U700") (pin "A7") (pinfunction "_DQ12_A7") (pintype "bidirectional"))
    )
    (net (code "41") (name "/DDR_DQ7") (class "Default")
      (node (ref "U700") (pin "D7") (pinfunction "_DQ8_D7") (pintype "bidirectional"))
    )
    (net (code "42") (name "/DDR_DQ8") (class "Default")
      (node (ref "U700") (pin "F2") (pinfunction "_DQ2_F2") (pintype "bidirectional"))
    )
    (net (code "43") (name "/DDR_DQ9") (class "Default")
      (node (ref "U700") (pin "H3") (pinfunction "_DQ4_H3") (pintype "bidirectional"))
    )
    (net (code "44") (name "/DDR_DQ10") (class "Default")
      (node (ref "U700") (pin "G2") (pinfunction "_DQ6_G2") (pintype "bidirectional"))
    )
    (net (code "45") (name "/DDR_DQ11") (class "Default")
      (node (ref "U700") (pin "F7") (pinfunction "_DQ1_F7") (pintype "bidirectional"))
    )
    (net (code "46") (name "/DDR_DQ12") (class "Default")
      (node (ref "U700") (pin "E3") (pinfunction "_DQ0_E3") (pintype "bidirectional"))
    )
    (net (code "47") (name "/DDR_DQ13") (class "Default")
      (node (ref "U700") (pin "H7") (pinfunction "_DQ7_H7") (pintype "bidirectional"))
    )
    (net (code "48") (name "/DDR_DQ14") (class "Default")
      (node (ref "U700") (pin "H8") (pinfunction "_DQ5_H8") (pintype "bidirectional"))
    )
    (net (code "49") (name "/DDR_DQ15") (class "Default")
      (node (ref "U700") (pin "F8") (pinfunction "_DQ3_F8") (pintype "bidirectional"))
    )
    (net (code "50") (name "/DDR_DQ16") (class "Default")
      (node (ref "U701") (pin "G2") (pinfunction "_DQ6_G2") (pintype "bidirectional"))
    )
    (net (code "51") (name "/DDR_DQ17") (class "Default")
      (node (ref "U701") (pin "H3") (pinfunction "_DQ4_H3") (pintype "bidirectional"))
    )
    (net (code "52") (name "/DDR_DQ18") (class "Default")
      (node (ref "U701") (pin "F2") (pinfunction "_DQ2_F2") (pintype "bidirectional"))
    )
    (net (code "53") (name "/DDR_DQ19") (class "Default")
      (node (ref "U701") (pin "E3") (pinfunction "_DQ0_E3") (pintype "bidirectional"))
    )
    (net (code "54") (name "/DDR_DQ20") (class "Default")
      (node (ref "U701") (pin "H7") (pinfunction "_DQ7_H7") (pintype "bidirectional"))
    )
    (net (code "55") (name "/DDR_DQ21") (class "Default")
      (node (ref "U701") (pin "H8") (pinfunction "_DQ5_H8") (pintype "bidirectional"))
    )
    (net (code "56") (name "/DDR_DQ22") (class "Default")
      (node (ref "U701") (pin "F7") (pinfunction "_DQ1_F7") (pintype "bidirectional"))
    )
    (net (code "57") (name "/DDR_DQ23") (class "Default")
      (node (ref "U701") (pin "F8") (pinfunction "_DQ4_F8") (pintype "bidirectional"))
    )
    (net (code "58") (name "/DDR_DQ24") (class "Default")
      (node (ref "U701") (pin "C2") (pinfunction "_DQ11_C2") (pintype "bidirectional"))
    )
    (net (code "59") (name "/DDR_DQ25") (class "Default")
      (node (ref "U701") (pin "C8") (pinfunction "_DQ10_C8") (pintype "bidirectional"))
    )
    (net (code "60") (name "/DDR_DQ26") (class "Default")
      (node (ref "U701") (pin "A3") (pinfunction "_DQ15_A3") (pintype "bidirectional"))
    )
    (net (code "61") (name "/DDR_DQ27") (class "Default")
      (node (ref "U701") (pin "B8") (pinfunction "_DQ14_B8") (pintype "bidirectional"))
    )
    (net (code "62") (name "/DDR_DQ28") (class "Default")
      (node (ref "U701") (pin "C3") (pinfunction "_DQ9_C3") (pintype "bidirectional"))
    )
    (net (code "63") (name "/DDR_DQ29") (class "Default")
      (node (ref "U701") (pin "A7") (pinfunction "_DQ12_A7") (pintype "bidirectional"))
    )
    (net (code "64") (name "/DDR_DQ30") (class "Default")
      (node (ref "U701") (pin "A2") (pinfunction "_DQ13_A2") (pintype "bidirectional"))
    )
    (net (code "65") (name "/DDR_DQ31") (class "Default")
      (node (ref "U701") (pin "D7") (pinfunction "_DQ8_D7") (pintype "bidirectional"))
    )
    (net (code "66") (name "/DDR_DQS0_N") (class "Default")
      (node (ref "U700") (pin "B7") (pinfunction "_UDQS#_B7") (pintype "bidirectional"))
    )
    (net (code "67") (name "/DDR_DQS0_P") (class "Default")
      (node (ref "U700") (pin "C7") (pinfunction "_UDQS_C7") (pintype "bidirectional"))
    )
    (net (code "68") (name "/DDR_DQS1_N") (class "Default")
      (node (ref "U700") (pin "G3") (pinfunction "_LDQS#_G3") (pintype "bidirectional"))
    )
    (net (code "69") (name "/DDR_DQS1_P") (class "Default")
      (node (ref "U700") (pin "F3") (pinfunction "_LDQS_F3") (pintype "bidirectional"))
    )
    (net (code "70") (name "/DDR_DQS2_N") (class "Default")
      (node (ref "U701") (pin "G3") (pinfunction "_LDQS#_G3") (pintype "bidirectional"))
    )
    (net (code "71") (name "/DDR_DQS2_P") (class "Default")
      (node (ref "U701") (pin "F3") (pinfunction "_LDQS_F3") (pintype "bidirectional"))
    )
    (net (code "72") (name "/DDR_DQS3_N") (class "Default")
      (node (ref "U701") (pin "B7") (pinfunction "_UDQS#_B7") (pintype "bidirectional"))
    )
    (net (code "73") (name "/DDR_DQS3_P") (class "Default")
      (node (ref "U701") (pin "C7") (pinfunction "_UDQS_C7") (pintype "bidirectional"))
    )
    (net (code "74") (name "/DDR_DRST_B") (class "Default")
      (node (ref "U700") (pin "T2") (pinfunction "_RESET#_T2") (pintype "input"))
      (node (ref "U701") (pin "T2") (pinfunction "_RESET#_T2") (pintype "input"))
    )
    (net (code "75") (name "/DDR_ODT") (class "Default")
      (node (ref "U700") (pin "K1") (pinfunction "_ODT_K1") (pintype "input"))
      (node (ref "U701") (pin "K1") (pinfunction "_ODT_K1") (pintype "input"))
    )
    (net (code "76") (name "/DDR_RAS_B") (class "Default")
      (node (ref "U700") (pin "J3") (pinfunction "RAS#_J3") (pintype "input"))
      (node (ref "U701") (pin "J3") (pinfunction "RAS#_J3") (pintype "input"))
    )
    (net (code "77") (name "/DDR_WE_B") (class "Default")
      (node (ref "U700") (pin "L3") (pinfunction "WE#_L3") (pintype "input"))
      (node (ref "U701") (pin "L3") (pinfunction "WE#_L3") (pintype "input"))
    )
    (net (code "78") (name "/DDR_ZQ_1") (class "Default")
      (node (ref "R700") (pin "2") (pinfunction "2_2") (pintype "passive"))
      (node (ref "U700") (pin "L8") (pinfunction "ZQ_L8") (pintype "input"))
    )
    (net (code "79") (name "/DDR_ZQ_2") (class "Default")
      (node (ref "R701") (pin "2") (pinfunction "2_2") (pintype "passive"))
      (node (ref "U701") (pin "L8") (pinfunction "ZQ_L8") (pintype "input"))
    )
    (net (code "85") (name "GND") (class "Default")
      (node (ref "C701") (pin "1") (pinfunction "1_1") (pintype "passive"))
      (node (ref "C702") (pin "1") (pinfunction "1_1") (pintype "passive"))
      (node (ref "C703") (pin "1") (pinfunction "1_1") (pintype "passive"))
      (node (ref "C704") (pin "1") (pinfunction "1_1") (pintype "passive"))
      (node (ref "C705") (pin "1") (pinfunction "1_1") (pintype "passive"))
      (node (ref "C707") (pin "1") (pinfunction "1_1") (pintype "passive"))
      (node (ref "C708") (pin "1") (pinfunction "1_1") (pintype "passive"))
      (node (ref "C709") (pin "1") (pinfunction "1_1") (pintype "passive"))
      (node (ref "C710") (pin "1") (pinfunction "1_1") (pintype "passive"))
      (node (ref "C711") (pin "1") (pinfunction "1_1") (pintype "passive"))
      (node (ref "C712") (pin "1") (pinfunction "1_1") (pintype "passive"))
      (node (ref "C713") (pin "1") (pinfunction "1_1") (pintype "passive"))
      (node (ref "C714") (pin "1") (pinfunction "1_1") (pintype "passive"))
      (node (ref "C715") (pin "1") (pinfunction "1_1") (pintype "passive"))
      (node (ref "C716") (pin "1") (pinfunction "1_1") (pintype "passive"))
      (node (ref "C717") (pin "1") (pinfunction "1_1") (pintype "passive"))
      (node (ref "C718") (pin "1") (pinfunction "1_1") (pintype "passive"))
      (node (ref "C719") (pin "1") (pinfunction "1_1") (pintype "passive"))
      (node (ref "C720") (pin "1") (pinfunction "1_1") (pintype "passive"))
      (node (ref "C721") (pin "1") (pinfunction "1_1") (pintype "passive"))
      (node (ref "C722") (pin "1") (pinfunction "1_1") (pintype "passive"))
      (node (ref "C723") (pin "1") (pinfunction "1_1") (pintype "passive"))
      (node (ref "C725") (pin "1") (pinfunction "1_1") (pintype "passive"))
      (node (ref "C726") (pin "1") (pinfunction "1_1") (pintype "passive"))
      (node (ref "C727") (pin "1") (pinfunction "1_1") (pintype "passive"))
      (node (ref "C728") (pin "1") (pinfunction "1_1") (pintype "passive"))
      (node (ref "C729") (pin "1") (pinfunction "1_1") (pintype "passive"))
      (node (ref "C731") (pin "1") (pinfunction "1_1") (pintype "passive"))
      (node (ref "C732") (pin "1") (pinfunction "1_1") (pintype "passive"))
      (node (ref "C733") (pin "1") (pinfunction "1_1") (pintype "passive"))
      (node (ref "C734") (pin "1") (pinfunction "1_1") (pintype "passive"))
      (node (ref "C735") (pin "1") (pinfunction "1_1") (pintype "passive"))
      (node (ref "C736") (pin "1") (pinfunction "1_1") (pintype "passive"))
      (node (ref "C737") (pin "1") (pinfunction "1_1") (pintype "passive"))
      (node (ref "C738") (pin "1") (pinfunction "1_1") (pintype "passive"))
      (node (ref "C739") (pin "1") (pinfunction "1_1") (pintype "passive"))
      (node (ref "C740") (pin "1") (pinfunction "1_1") (pintype "passive"))
      (node (ref "C741") (pin "1") (pinfunction "1_1") (pintype "passive"))
      (node (ref "C742") (pin "1") (pinfunction "1_1") (pintype "passive"))
      (node (ref "C743") (pin "1") (pinfunction "1_1") (pintype "passive"))
      (node (ref "C744") (pin "1") (pinfunction "1_1") (pintype "passive"))
      (node (ref "C745") (pin "1") (pinfunction "1_1") (pintype "passive"))
      (node (ref "R700") (pin "1") (pinfunction "1_1") (pintype "passive"))
      (node (ref "R701") (pin "1") (pinfunction "1_1") (pintype "passive"))
      (node (ref "U700") (pin "A9") (pinfunction "_VSS_A9") (pintype "input"))
      (node (ref "U700") (pin "B1") (pinfunction "_VSSQ_B1") (pintype "input"))
      (node (ref "U700") (pin "B3") (pinfunction "_VSS_B3") (pintype "input"))
      (node (ref "U700") (pin "B9") (pinfunction "_VSSQ_B9") (pintype "input"))
      (node (ref "U700") (pin "D1") (pinfunction "_VSSQ_D1") (pintype "input"))
      (node (ref "U700") (pin "D8") (pinfunction "_VSSQ_D8") (pintype "input"))
      (node (ref "U700") (pin "E1") (pinfunction "_VSS_E1") (pintype "input"))
      (node (ref "U700") (pin "E2") (pinfunction "_VSSQ_E2") (pintype "input"))
      (node (ref "U700") (pin "E8") (pinfunction "_VSSQ_E8") (pintype "input"))
      (node (ref "U700") (pin "F9") (pinfunction "_VSSQ_F9") (pintype "input"))
      (node (ref "U700") (pin "G1") (pinfunction "_VSSQ_G1") (pintype "input"))
      (node (ref "U700") (pin "G8") (pinfunction "_VSS_G8") (pintype "input"))
      (node (ref "U700") (pin "G9") (pinfunction "_VSSQ_G9") (pintype "input"))
      (node (ref "U700") (pin "J2") (pinfunction "_VSS_J2") (pintype "input"))
      (node (ref "U700") (pin "J8") (pinfunction "_VSS_J8") (pintype "input"))
      (node (ref "U700") (pin "M1") (pinfunction "_VSS_M1") (pintype "input"))
      (node (ref "U700") (pin "M9") (pinfunction "_VSS_M9") (pintype "input"))
      (node (ref "U700") (pin "P1") (pinfunction "_VSS_P1") (pintype "input"))
      (node (ref "U700") (pin "P9") (pinfunction "_VSS_P9") (pintype "input"))
      (node (ref "U700") (pin "T1") (pinfunction "_VSS_T1") (pintype "input"))
      (node (ref "U700") (pin "T9") (pinfunction "_VSS_T9") (pintype "input"))
      (node (ref "U701") (pin "A9") (pinfunction "_VSS_A9") (pintype "input"))
      (node (ref "U701") (pin "B1") (pinfunction "_VSSQ_B1") (pintype "input"))
      (node (ref "U701") (pin "B3") (pinfunction "_VSS_B3") (pintype "input"))
      (node (ref "U701") (pin "B9") (pinfunction "_VSSQ_B9") (pintype "input"))
      (node (ref "U701") (pin "D1") (pinfunction "_VSSQ_D1") (pintype "input"))
      (node (ref "U701") (pin "D8") (pinfunction "_VSSQ_D8") (pintype "input"))
      (node (ref "U701") (pin "E1") (pinfunction "_VSS_E1") (pintype "input"))
      (node (ref "U701") (pin "E2") (pinfunction "_VSSQ_E2") (pintype "input"))
      (node (ref "U701") (pin "E8") (pinfunction "_VSSQ_E8") (pintype "input"))
      (node (ref "U701") (pin "F9") (pinfunction "_VSSQ_F9") (pintype "input"))
      (node (ref "U701") (pin "G1") (pinfunction "_VSSQ_G1") (pintype "input"))
      (node (ref "U701") (pin "G8") (pinfunction "_VSS_G8") (pintype "input"))
      (node (ref "U701") (pin "G9") (pinfunction "_VSSQ_G9") (pintype "input"))
      (node (ref "U701") (pin "J2") (pinfunction "_VSS_J2") (pintype "input"))
      (node (ref "U701") (pin "J8") (pinfunction "_VSS_J8") (pintype "input"))
      (node (ref "U701") (pin "M1") (pinfunction "_VSS_M1") (pintype "input"))
      (node (ref "U701") (pin "M9") (pinfunction "_VSS_M9") (pintype "input"))
      (node (ref "U701") (pin "P1") (pinfunction "_VSS_P1") (pintype "input"))
      (node (ref "U701") (pin "P9") (pinfunction "_VSS_P9") (pintype "input"))
      (node (ref "U701") (pin "T1") (pinfunction "_VSS_T1") (pintype "input"))
      (node (ref "U701") (pin "T9") (pinfunction "_VSS_T9") (pintype "input"))
    )
    (net (code "86") (name "VTT_REF") (class "Default")
      (node (ref "C712") (pin "2") (pinfunction "2_2") (pintype "passive"))
      (node (ref "C713") (pin "2") (pinfunction "2_2") (pintype "passive"))
      (node (ref "U700") (pin "H1") (pinfunction "_VREFDQ_H1") (pintype "input"))
      (node (ref "U700") (pin "M8") (pinfunction "_VREFCA_M8") (pintype "input"))
      (node (ref "U701") (pin "H1") (pinfunction "_VREFDQ_H1") (pintype "input"))
      (node (ref "U701") (pin "M8") (pinfunction "_VREFCA_M8") (pintype "input"))
    )
    (net (code "87") (name "unconnected-(U700B-_NC-PadJ1)") (class "Default")
      (node (ref "U700") (pin "J1") (pinfunction "_NC_J1") (pintype "input+no_connect"))
    )
    (net (code "88") (name "unconnected-(U700B-_NC-PadJ9)") (class "Default")
      (node (ref "U700") (pin "J9") (pinfunction "_NC_J9") (pintype "input+no_connect"))
    )
    (net (code "89") (name "unconnected-(U700B-_NC-PadL1)") (class "Default")
      (node (ref "U700") (pin "L1") (pinfunction "_NC_L1") (pintype "input+no_connect"))
    )
    (net (code "90") (name "unconnected-(U700B-_NC-PadL9)") (class "Default")
      (node (ref "U700") (pin "L9") (pinfunction "_NC_L9") (pintype "input+no_connect"))
    )
    (net (code "91") (name "unconnected-(U700B-_NC-PadM7)") (class "Default")
      (node (ref "U700") (pin "M7") (pinfunction "_NC_M7") (pintype "input+no_connect"))
    )
    (net (code "92") (name "unconnected-(U701B-_NC-PadJ1)") (class "Default")
      (node (ref "U701") (pin "J1") (pinfunction "_NC_J1") (pintype "input+no_connect"))
    )
    (net (code "93") (name "unconnected-(U701B-_NC-PadJ9)") (class "Default")
      (node (ref "U701") (pin "J9") (pinfunction "_NC_J9") (pintype "input+no_connect"))
    )
    (net (code "94") (name "unconnected-(U701B-_NC-PadL1)") (class "Default")
      (node (ref "U701") (pin "L1") (pinfunction "_NC_L1") (pintype "input+no_connect"))
    )
    (net (code "95") (name "unconnected-(U701B-_NC-PadL9)") (class "Default")
      (node (ref "U701") (pin "L9") (pinfunction "_NC_L9") (pintype "input+no_connect"))
    )
    (net (code "96") (name "unconnected-(U701B-_NC-PadM7)") (class "Default")
      (node (ref "U701") (pin "M7") (pinfunction "_NC_M7") (pintype "input+no_connect"))
    )
  )
)
